# OmniCar_v0_1.net
KiCad netlist of a schematic drawn in EAGLE
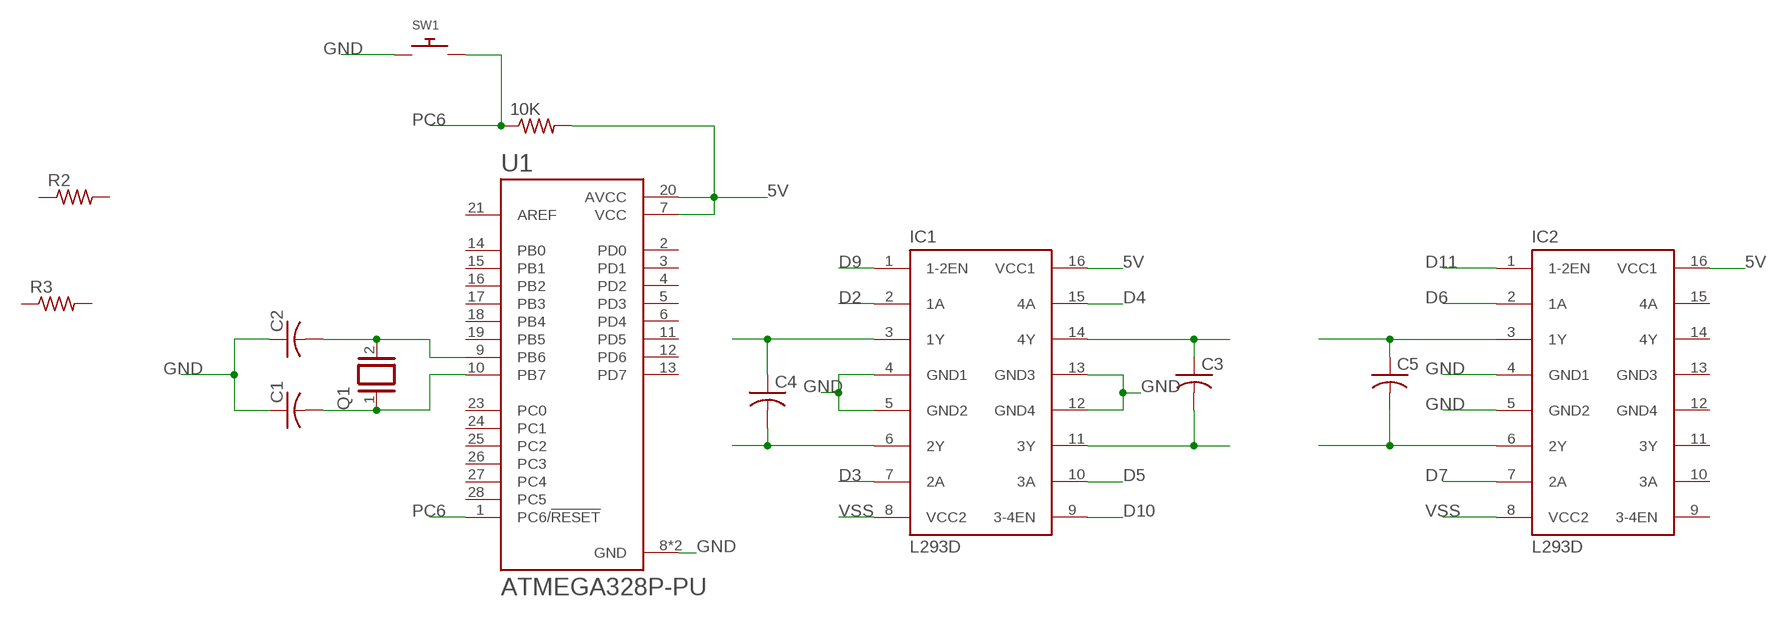
[diagram p0: schematic, sheet 1]

(export (version "E")
  (design (tool "Eeschema 10.0.6"))
  (components
    (comp (ref "10K")
      (value "R-US_0204/5")
      (footprint "eagle-import:0204_5")
      (libsource (lib "eagle-import") (part "R-US_0204/5"))
    )
    (comp (ref "C1")
      (value "C-US025-030X050")
      (footprint "eagle-import:C025-030X050")
      (libsource (lib "eagle-import") (part "C-US025-030X050"))
    )
    (comp (ref "C2")
      (value "C-US025-030X050")
      (footprint "eagle-import:C025-030X050")
      (libsource (lib "eagle-import") (part "C-US025-030X050"))
    )
    (comp (ref "C3")
      (value "C-US025-030X050")
      (footprint "eagle-import:C025-030X050")
      (libsource (lib "eagle-import") (part "C-US025-030X050"))
    )
    (comp (ref "C4")
      (value "C-US025-030X050")
      (footprint "eagle-import:C025-030X050")
      (libsource (lib "eagle-import") (part "C-US025-030X050"))
    )
    (comp (ref "C5")
      (value "C-US025-030X050")
      (footprint "eagle-import:C025-030X050")
      (libsource (lib "eagle-import") (part "C-US025-030X050"))
    )
    (comp (ref "IC1")
      (value "L293D")
      (footprint "eagle-import:DIL16")
      (fields (field (name "MF") "STMicroelectronics"))
      (libsource (lib "eagle-import") (part "L293D"))
    )
    (comp (ref "IC2")
      (value "L293D")
      (footprint "eagle-import:DIL16")
      (fields (field (name "MF") "STMicroelectronics"))
      (libsource (lib "eagle-import") (part "L293D"))
    )
    (comp (ref "Q1")
      (value "XTAL")
      (footprint "eagle-import:Q")
      (libsource (lib "eagle-import") (part "XTAL"))
    )
    (comp (ref "R2")
      (value "R-US_0204/5")
      (footprint "eagle-import:0204_5")
      (libsource (lib "eagle-import") (part "R-US_0204/5"))
    )
    (comp (ref "R3")
      (value "R-US_0204/5")
      (footprint "eagle-import:0204_5")
      (libsource (lib "eagle-import") (part "R-US_0204/5"))
    )
    (comp (ref "SW1")
      (value "SWITCH_PUSHBUTTONEVQ-PE")
      (footprint "eagle-import:TACT_PANA-EVQ")
      (libsource (lib "eagle-import") (part "SWITCH_PUSHBUTTONEVQ-PE"))
    )
    (comp (ref "U1")
      (value "ATMEGA328P-PU")
      (footprint "eagle-import:DIP794W46P254L2967H457Q28B")
      (fields (field (name "MF") "Microchip"))
      (libsource (lib "eagle-import") (part "ATMEGA328P-PU"))
    )
  )
  (nets
    (net (code "1") (name "/5V") (class "Default")
      (node (ref "10K") (pin "2") (pinfunction "2_2") (pintype "passive"))
      (node (ref "IC1") (pin "16") (pinfunction "VCC1_16") (pintype "power_in"))
      (node (ref "IC2") (pin "16") (pinfunction "VCC1_16") (pintype "power_in"))
      (node (ref "U1") (pin "20") (pinfunction "AVCC_20") (pintype "power_in"))
      (node (ref "U1") (pin "7") (pinfunction "VCC_7") (pintype "power_in"))
    )
    (net (code "2") (name "/D2") (class "Default")
      (node (ref "IC1") (pin "2") (pinfunction "1A_2") (pintype "input"))
    )
    (net (code "3") (name "/D3") (class "Default")
      (node (ref "IC1") (pin "7") (pinfunction "2A_7") (pintype "input"))
    )
    (net (code "4") (name "/D4") (class "Default")
      (node (ref "IC1") (pin "15") (pinfunction "4A_15") (pintype "input"))
    )
    (net (code "5") (name "/D5") (class "Default")
      (node (ref "IC1") (pin "10") (pinfunction "3A_10") (pintype "input"))
    )
    (net (code "6") (name "/D6") (class "Default")
      (node (ref "IC2") (pin "2") (pinfunction "1A_2") (pintype "input"))
    )
    (net (code "7") (name "/D7") (class "Default")
      (node (ref "IC2") (pin "7") (pinfunction "2A_7") (pintype "input"))
    )
    (net (code "8") (name "/D9") (class "Default")
      (node (ref "IC1") (pin "1") (pinfunction "1-2EN_1") (pintype "input"))
    )
    (net (code "9") (name "/D10") (class "Default")
      (node (ref "IC1") (pin "9") (pinfunction "3-4EN_9") (pintype "input"))
    )
    (net (code "10") (name "/D11") (class "Default")
      (node (ref "IC2") (pin "1") (pinfunction "1-2EN_1") (pintype "input"))
    )
    (net (code "11") (name "/GND") (class "Default")
      (node (ref "C1") (pin "1") (pinfunction "1_1") (pintype "passive"))
      (node (ref "C2") (pin "1") (pinfunction "1_1") (pintype "passive"))
      (node (ref "IC1") (pin "12") (pinfunction "GND4_12") (pintype "power_in"))
      (node (ref "IC1") (pin "13") (pinfunction "GND3_13") (pintype "power_in"))
      (node (ref "IC1") (pin "4") (pinfunction "GND1_4") (pintype "power_in"))
      (node (ref "IC1") (pin "5") (pinfunction "GND2_5") (pintype "power_in"))
      (node (ref "IC2") (pin "4") (pinfunction "GND1_4") (pintype "power_in"))
      (node (ref "IC2") (pin "5") (pinfunction "GND2_5") (pintype "power_in"))
      (node (ref "SW1") (pin "P$1") (pinfunction "P$1_P$1") (pintype "passive"))
      (node (ref "U1") (pin "22") (pinfunction "GND_22") (pintype "power_in"))
      (node (ref "U1") (pin "8") (pinfunction "GND_8") (pintype "power_in"))
    )
    (net (code "12") (name "/GND3") (class "Default")
      (node (ref "IC2") (pin "13") (pinfunction "GND3_13") (pintype "power_in"))
    )
    (net (code "13") (name "/GND4") (class "Default")
      (node (ref "IC2") (pin "12") (pinfunction "GND4_12") (pintype "power_in"))
    )
    (net (code "14") (name "/PC6") (class "Default")
      (node (ref "10K") (pin "1") (pinfunction "1_1") (pintype "passive"))
      (node (ref "SW1") (pin "P$2") (pinfunction "P$2_P$2") (pintype "passive"))
      (node (ref "U1") (pin "1") (pinfunction "PC6/~{RESET}_1") (pintype "bidirectional"))
    )
    (net (code "15") (name "/VSS") (class "Default")
      (node (ref "IC1") (pin "8") (pinfunction "VCC2_8") (pintype "power_in"))
      (node (ref "IC2") (pin "8") (pinfunction "VCC2_8") (pintype "power_in"))
    )
    (net (code "16") (name "Net-(IC1-1Y)") (class "Default")
      (node (ref "C4") (pin "1") (pinfunction "1_1") (pintype "passive"))
      (node (ref "IC1") (pin "3") (pinfunction "1Y_3") (pintype "output"))
    )
    (net (code "17") (name "Net-(IC1-2Y)") (class "Default")
      (node (ref "C4") (pin "2") (pinfunction "2_2") (pintype "passive"))
      (node (ref "IC1") (pin "6") (pinfunction "2Y_6") (pintype "output"))
    )
    (net (code "18") (name "Net-(IC1-3Y)") (class "Default")
      (node (ref "C3") (pin "2") (pinfunction "2_2") (pintype "passive"))
      (node (ref "IC1") (pin "11") (pinfunction "3Y_11") (pintype "output"))
    )
    (net (code "19") (name "Net-(IC1-4Y)") (class "Default")
      (node (ref "C3") (pin "1") (pinfunction "1_1") (pintype "passive"))
      (node (ref "IC1") (pin "14") (pinfunction "4Y_14") (pintype "output"))
    )
    (net (code "20") (name "Net-(IC2-1Y)") (class "Default")
      (node (ref "C5") (pin "1") (pinfunction "1_1") (pintype "passive"))
      (node (ref "IC2") (pin "3") (pinfunction "1Y_3") (pintype "output"))
    )
    (net (code "21") (name "Net-(IC2-2Y)") (class "Default")
      (node (ref "C5") (pin "2") (pinfunction "2_2") (pintype "passive"))
      (node (ref "IC2") (pin "6") (pinfunction "2Y_6") (pintype "output"))
    )
    (net (code "22") (name "Net-(U1-PB6)") (class "Default")
      (node (ref "C2") (pin "2") (pinfunction "2_2") (pintype "passive"))
      (node (ref "Q1") (pin "2") (pinfunction "2_2") (pintype "passive"))
      (node (ref "U1") (pin "9") (pinfunction "PB6_9") (pintype "bidirectional"))
    )
    (net (code "23") (name "Net-(U1-PB7)") (class "Default")
      (node (ref "C1") (pin "2") (pinfunction "2_2") (pintype "passive"))
      (node (ref "Q1") (pin "1") (pinfunction "1_1") (pintype "passive"))
      (node (ref "U1") (pin "10") (pinfunction "PB7_10") (pintype "bidirectional"))
    )
    (net (code "24") (name "unconnected-(IC2-3-4EN-Pad9)") (class "Default")
      (node (ref "IC2") (pin "9") (pinfunction "3-4EN_9") (pintype "input"))
    )
    (net (code "25") (name "unconnected-(IC2-3A-Pad10)") (class "Default")
      (node (ref "IC2") (pin "10") (pinfunction "3A_10") (pintype "input"))
    )
    (net (code "26") (name "unconnected-(IC2-3Y-Pad11)") (class "Default")
      (node (ref "IC2") (pin "11") (pinfunction "3Y_11") (pintype "output"))
    )
    (net (code "27") (name "unconnected-(IC2-4A-Pad15)") (class "Default")
      (node (ref "IC2") (pin "15") (pinfunction "4A_15") (pintype "input"))
    )
    (net (code "28") (name "unconnected-(IC2-4Y-Pad14)") (class "Default")
      (node (ref "IC2") (pin "14") (pinfunction "4Y_14") (pintype "output"))
    )
    (net (code "29") (name "unconnected-(R2-Pad1)") (class "Default")
      (node (ref "R2") (pin "1") (pinfunction "1_1") (pintype "passive"))
    )
    (net (code "30") (name "unconnected-(R2-Pad2)") (class "Default")
      (node (ref "R2") (pin "2") (pinfunction "2_2") (pintype "passive"))
    )
    (net (code "31") (name "unconnected-(R3-Pad1)") (class "Default")
      (node (ref "R3") (pin "1") (pinfunction "1_1") (pintype "passive"))
    )
    (net (code "32") (name "unconnected-(R3-Pad2)") (class "Default")
      (node (ref "R3") (pin "2") (pinfunction "2_2") (pintype "passive"))
    )
    (net (code "33") (name "unconnected-(U1-AREF-Pad21)") (class "Default")
      (node (ref "U1") (pin "21") (pinfunction "AREF_21") (pintype "input"))
    )
    (net (code "34") (name "unconnected-(U1-PB0-Pad14)") (class "Default")
      (node (ref "U1") (pin "14") (pinfunction "PB0_14") (pintype "bidirectional"))
    )
    (net (code "35") (name "unconnected-(U1-PB1-Pad15)") (class "Default")
      (node (ref "U1") (pin "15") (pinfunction "PB1_15") (pintype "bidirectional"))
    )
    (net (code "36") (name "unconnected-(U1-PB2-Pad16)") (class "Default")
      (node (ref "U1") (pin "16") (pinfunction "PB2_16") (pintype "bidirectional"))
    )
    (net (code "37") (name "unconnected-(U1-PB3-Pad17)") (class "Default")
      (node (ref "U1") (pin "17") (pinfunction "PB3_17") (pintype "bidirectional"))
    )
    (net (code "38") (name "unconnected-(U1-PB4-Pad18)") (class "Default")
      (node (ref "U1") (pin "18") (pinfunction "PB4_18") (pintype "bidirectional"))
    )
    (net (code "39") (name "unconnected-(U1-PB5-Pad19)") (class "Default")
      (node (ref "U1") (pin "19") (pinfunction "PB5_19") (pintype "bidirectional"))
    )
    (net (code "40") (name "unconnected-(U1-PC0-Pad23)") (class "Default")
      (node (ref "U1") (pin "23") (pinfunction "PC0_23") (pintype "bidirectional"))
    )
    (net (code "41") (name "unconnected-(U1-PC1-Pad24)") (class "Default")
      (node (ref "U1") (pin "24") (pinfunction "PC1_24") (pintype "bidirectional"))
    )
    (net (code "42") (name "unconnected-(U1-PC2-Pad25)") (class "Default")
      (node (ref "U1") (pin "25") (pinfunction "PC2_25") (pintype "bidirectional"))
    )
    (net (code "43") (name "unconnected-(U1-PC3-Pad26)") (class "Default")
      (node (ref "U1") (pin "26") (pinfunction "PC3_26") (pintype "bidirectional"))
    )
    (net (code "44") (name "unconnected-(U1-PC4-Pad27)") (class "Default")
      (node (ref "U1") (pin "27") (pinfunction "PC4_27") (pintype "bidirectional"))
    )
    (net (code "45") (name "unconnected-(U1-PC5-Pad28)") (class "Default")
      (node (ref "U1") (pin "28") (pinfunction "PC5_28") (pintype "bidirectional"))
    )
    (net (code "46") (name "unconnected-(U1-PD0-Pad2)") (class "Default")
      (node (ref "U1") (pin "2") (pinfunction "PD0_2") (pintype "bidirectional"))
    )
    (net (code "47") (name "unconnected-(U1-PD1-Pad3)") (class "Default")
      (node (ref "U1") (pin "3") (pinfunction "PD1_3") (pintype "bidirectional"))
    )
    (net (code "48") (name "unconnected-(U1-PD2-Pad4)") (class "Default")
      (node (ref "U1") (pin "4") (pinfunction "PD2_4") (pintype "bidirectional"))
    )
    (net (code "49") (name "unconnected-(U1-PD3-Pad5)") (class "Default")
      (node (ref "U1") (pin "5") (pinfunction "PD3_5") (pintype "bidirectional"))
    )
    (net (code "50") (name "unconnected-(U1-PD4-Pad6)") (class "Default")
      (node (ref "U1") (pin "6") (pinfunction "PD4_6") (pintype "bidirectional"))
    )
    (net (code "51") (name "unconnected-(U1-PD5-Pad11)") (class "Default")
      (node (ref "U1") (pin "11") (pinfunction "PD5_11") (pintype "bidirectional"))
    )
    (net (code "52") (name "unconnected-(U1-PD6-Pad12)") (class "Default")
      (node (ref "U1") (pin "12") (pinfunction "PD6_12") (pintype "bidirectional"))
    )
    (net (code "53") (name "unconnected-(U1-PD7-Pad13)") (class "Default")
      (node (ref "U1") (pin "13") (pinfunction "PD7_13") (pintype "bidirectional"))
    )
  )
)
